# ADS1256.net
KiCad netlist of a schematic drawn in Altium Designer
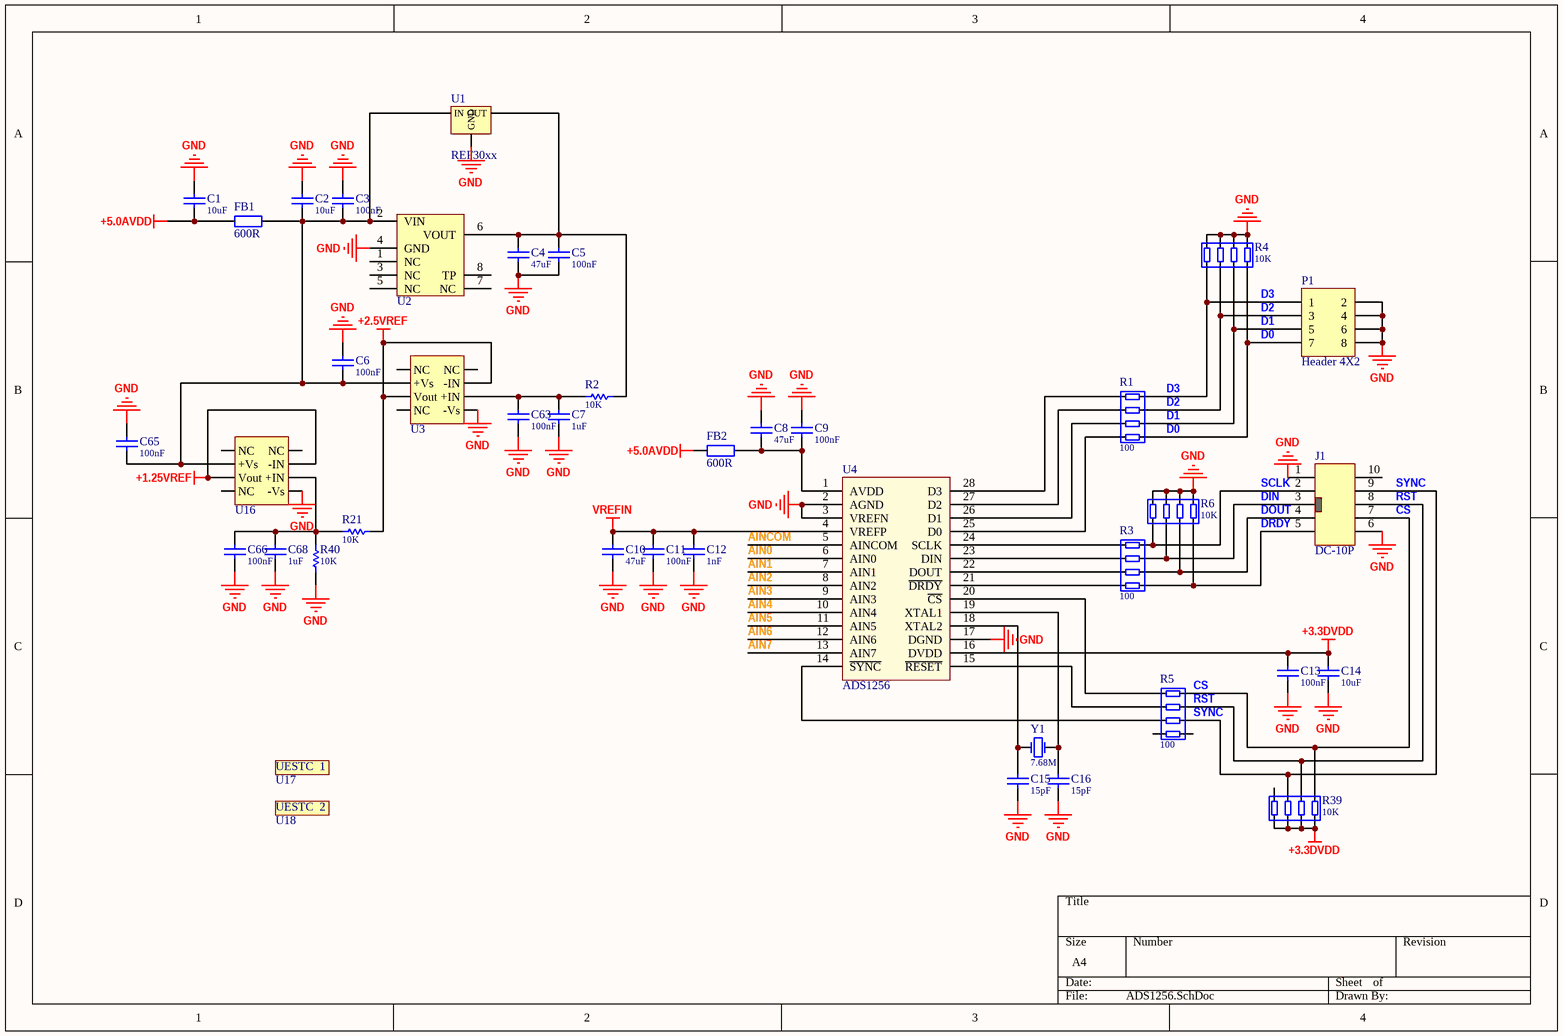
[diagram p0: ADS1256.SchDoc]

(export (version "E")
  (design (tool "Eeschema 10.0.6"))
  (components
    (comp (ref "C1")
      (value "10uF")
      (footprint "C0603-L")
      (description "贴片瓷片电容")
      (fields (field (name "Comment") "Cap-S"))
      (libsource (lib "xz_D") (part "Cap-S"))
    )
    (comp (ref "C2")
      (value "10uF")
      (footprint "C0603-L")
      (description "贴片瓷片电容")
      (fields (field (name "Comment") "Cap-S"))
      (libsource (lib "xz_D") (part "Cap-S"))
    )
    (comp (ref "C3")
      (value "100nF")
      (footprint "C0402-L")
      (description "贴片瓷片电容")
      (fields (field (name "Comment") "Cap-S"))
      (libsource (lib "xz_D") (part "Cap-S"))
    )
    (comp (ref "C4")
      (value "47uF")
      (footprint "C0805-L")
      (description "贴片瓷片电容")
      (fields (field (name "Comment") "Cap-S"))
      (libsource (lib "xz_D") (part "Cap-S"))
    )
    (comp (ref "C5")
      (value "100nF")
      (footprint "C0402-L")
      (description "贴片瓷片电容")
      (fields (field (name "Comment") "Cap-S"))
      (libsource (lib "xz_D") (part "Cap-S"))
    )
    (comp (ref "C6")
      (value "100nF")
      (footprint "C0402-L")
      (description "贴片瓷片电容")
      (fields (field (name "Comment") "Cap-S"))
      (libsource (lib "xz_D") (part "Cap-S"))
    )
    (comp (ref "C7")
      (value "1uF")
      (footprint "C0603-L")
      (description "贴片瓷片电容")
      (fields (field (name "Comment") "Cap-S"))
      (libsource (lib "xz_D") (part "Cap-S"))
    )
    (comp (ref "C8")
      (value "47uF")
      (footprint "C0805-L")
      (description "贴片瓷片电容")
      (fields (field (name "Comment") "Cap-S"))
      (libsource (lib "xz_D") (part "Cap-S"))
    )
    (comp (ref "C9")
      (value "100nF")
      (footprint "C0402-L")
      (description "贴片瓷片电容")
      (fields (field (name "Comment") "Cap-S"))
      (libsource (lib "xz_D") (part "Cap-S"))
    )
    (comp (ref "C10")
      (value "47uF")
      (footprint "C0805-L")
      (description "贴片瓷片电容")
      (fields (field (name "Comment") "Cap-S"))
      (libsource (lib "xz_D") (part "Cap-S"))
    )
    (comp (ref "C11")
      (value "100nF")
      (footprint "C0402-L")
      (description "贴片瓷片电容")
      (fields (field (name "Comment") "Cap-S"))
      (libsource (lib "xz_D") (part "Cap-S"))
    )
    (comp (ref "C12")
      (value "1nF")
      (footprint "C0402-L")
      (description "贴片瓷片电容")
      (fields (field (name "Comment") "Cap-S"))
      (libsource (lib "xz_D") (part "Cap-S"))
    )
    (comp (ref "C13")
      (value "100nF")
      (footprint "C0402-L")
      (description "贴片瓷片电容")
      (fields (field (name "Comment") "Cap-S"))
      (libsource (lib "xz_D") (part "Cap-S"))
    )
    (comp (ref "C14")
      (value "10uF")
      (footprint "C0603-L")
      (description "贴片瓷片电容")
      (fields (field (name "Comment") "Cap-S"))
      (libsource (lib "xz_D") (part "Cap-S"))
    )
    (comp (ref "C15")
      (value "15pF")
      (footprint "C0603-L")
      (description "贴片瓷片电容")
      (fields (field (name "Comment") "Cap-S"))
      (libsource (lib "xz_D") (part "Cap-S"))
    )
    (comp (ref "C16")
      (value "15pF")
      (footprint "C0603-L")
      (description "贴片瓷片电容")
      (fields (field (name "Comment") "Cap-S"))
      (libsource (lib "xz_D") (part "Cap-S"))
    )
    (comp (ref "C63")
      (value "100nF")
      (footprint "C0402-L")
      (description "贴片瓷片电容")
      (fields (field (name "Comment") "Cap-S"))
      (libsource (lib "xz_D") (part "Cap-S"))
    )
    (comp (ref "C65")
      (value "100nF")
      (footprint "C0402-L")
      (description "贴片瓷片电容")
      (fields (field (name "Comment") "Cap-S"))
      (libsource (lib "xz_D") (part "Cap-S"))
    )
    (comp (ref "C66")
      (value "100nF")
      (footprint "C0402-L")
      (description "贴片瓷片电容")
      (fields (field (name "Comment") "Cap-S"))
      (libsource (lib "xz_D") (part "Cap-S"))
    )
    (comp (ref "C68")
      (value "1uF")
      (footprint "C0603-L")
      (description "贴片瓷片电容")
      (fields (field (name "Comment") "Cap-S"))
      (libsource (lib "xz_D") (part "Cap-S"))
    )
    (comp (ref "FB1") (value "600R") (footprint "FB-0805") (libsource (lib "CommonUsed") (part "FB")))
    (comp (ref "FB2") (value "600R") (footprint "FB-0805") (libsource (lib "CommonUsed") (part "FB")))
    (comp (ref "J1") (value "DC-10P") (footprint "DC-10P") (libsource (lib "CommonUsed") (part "DC-10P")))
    (comp (ref "P1")
      (value "Header 4X2")
      (footprint "HDR2X4")
      (description "Header, 4-Pin, Dual row")
      (fields (field (name "PUBLISHER") "Altium Limited"))
      (libsource (lib "xz_C") (part "Header 4X2"))
    )
    (comp (ref "R1")
      (value "100")
      (footprint "R0603X4")
      (description "排阻 4")
      (fields (field (name "Comment") "R"))
      (libsource (lib "xz_D") (part "Res-4R"))
    )
    (comp (ref "R2")
      (value "10K")
      (footprint "R0603-L")
      (description "贴片电阻")
      (fields (field (name "Comment") "R"))
      (libsource (lib "xz_D") (part "Res"))
    )
    (comp (ref "R3")
      (value "100")
      (footprint "R0603X4")
      (description "排阻 4")
      (fields (field (name "Comment") "R"))
      (libsource (lib "xz_D") (part "Res-4R"))
    )
    (comp (ref "R4")
      (value "10K")
      (footprint "R0603X4")
      (description "排阻 4")
      (fields (field (name "Comment") "R"))
      (libsource (lib "xz_D") (part "Res-4R"))
    )
    (comp (ref "R5")
      (value "100")
      (footprint "R0603X4")
      (description "排阻 4")
      (fields (field (name "Comment") "R"))
      (libsource (lib "xz_D") (part "Res-4R"))
    )
    (comp (ref "R6")
      (value "10K")
      (footprint "R0603X4")
      (description "排阻 4")
      (fields (field (name "Comment") "R"))
      (libsource (lib "xz_D") (part "Res-4R"))
    )
    (comp (ref "R21")
      (value "10K")
      (footprint "R0603-L")
      (description "贴片电阻")
      (fields (field (name "Comment") "R"))
      (libsource (lib "xz_D") (part "Res"))
    )
    (comp (ref "R39")
      (value "10K")
      (footprint "R0603X4")
      (description "排阻 4")
      (fields (field (name "Comment") "R"))
      (libsource (lib "xz_D") (part "Res-4R"))
    )
    (comp (ref "R40")
      (value "10K")
      (footprint "R0603-L")
      (description "贴片电阻")
      (fields (field (name "Comment") "R"))
      (libsource (lib "xz_D") (part "Res"))
    )
    (comp (ref "U1")
      (value "REF30xx")
      (footprint "SOT23-3_L")
      (description "采用 SOT23-3 封装的 2.5V 输出 50ppm/℃ 漂移 50uA 静态电流的（带隙）电压参考")
      (libsource (lib "CommonUsed") (part "REF3025"))
    )
    (comp (ref "U2")
      (value "ADR45xx")
      (footprint "SOIC-8_N")
      (description "超低噪声、高精度  基准电压源")
      (libsource (lib "xz_D") (part "ADR45xx"))
    )
    (comp (ref "U3")
      (value "OPA657")
      (footprint "SOIC-8_N")
      (description "1.6-GHz, Low-Noise, FET-Input Operational Amplifier")
      (fields (field (name "MANUFACTURER") "Texas Instruments") (field (name "PARTNUMBER") "OPA656U"))
      (libsource (lib "xz_D") (part "OPA657"))
    )
    (comp (ref "U4") (value "ADS1256") (footprint "TSSOP-28") (libsource (lib "CommonUsed") (part "ADS1256")))
    (comp (ref "U16")
      (value "OPA657")
      (footprint "SOIC-8_N")
      (description "1.6-GHz, Low-Noise, FET-Input Operational Amplifier")
      (fields (field (name "MANUFACTURER") "Texas Instruments") (field (name "PARTNUMBER") "OPA656U"))
      (libsource (lib "xz_D") (part "OPA657"))
    )
    (comp (ref "U17") (value "UESTC  1") (footprint "UESTC") (libsource (lib "CommonUsed") (part "UESTC  1")))
    (comp (ref "U18")
      (value "UESTC  2")
      (footprint "UESTC  2")
      (libsource (lib "CommonUsed") (part "UESTC  2"))
    )
    (comp (ref "Y1")
      (value "7.68M")
      (footprint "XTAL-PB2-SMD")
      (description "晶振")
      (fields (field (name "Comment") "XTAL"))
      (libsource (lib "xz_D") (part "XTAL"))
    )
  )
  (nets
    (net (code "1") (name "+1.25VREF") (class "Default")
      (node (ref "U16") (pin "2") (pinfunction "-IN_2") (pintype "passive"))
      (node (ref "U16") (pin "6") (pinfunction "Vout_6") (pintype "passive"))
    )
    (net (code "2") (name "+2.5VREF") (class "Default")
      (node (ref "R21") (pin "2") (pinfunction "2_2") (pintype "passive"))
      (node (ref "U3") (pin "2") (pinfunction "-IN_2") (pintype "passive"))
      (node (ref "U3") (pin "6") (pinfunction "Vout_6") (pintype "passive"))
    )
    (net (code "3") (name "+3.3DVDD") (class "Default")
      (node (ref "C13") (pin "2") (pinfunction "2_2") (pintype "passive"))
      (node (ref "C14") (pin "2") (pinfunction "2_2") (pintype "passive"))
      (node (ref "R39") (pin "1") (pintype "passive"))
      (node (ref "R39") (pin "2") (pintype "passive"))
      (node (ref "R39") (pin "3") (pintype "passive"))
      (node (ref "R39") (pin "4") (pintype "passive"))
      (node (ref "U4") (pin "16") (pinfunction "DVDD_16") (pintype "passive"))
    )
    (net (code "4") (name "+5.0AVDD") (class "Default")
      (node (ref "C1") (pin "1") (pinfunction "1_1") (pintype "passive"))
      (node (ref "FB1") (pin "1") (pinfunction "1_1") (pintype "passive"))
      (node (ref "FB2") (pin "1") (pinfunction "1_1") (pintype "passive"))
    )
    (net (code "5") (name "/AIN0") (class "Default")
      (node (ref "U4") (pin "6") (pinfunction "AIN0_6") (pintype "passive"))
    )
    (net (code "6") (name "/AIN1") (class "Default")
      (node (ref "U4") (pin "7") (pinfunction "AIN1_7") (pintype "passive"))
    )
    (net (code "7") (name "/AIN2") (class "Default")
      (node (ref "U4") (pin "8") (pinfunction "AIN2_8") (pintype "passive"))
    )
    (net (code "8") (name "/AIN3") (class "Default")
      (node (ref "U4") (pin "9") (pinfunction "AIN3_9") (pintype "passive"))
    )
    (net (code "9") (name "/AIN4") (class "Default")
      (node (ref "U4") (pin "10") (pinfunction "AIN4_10") (pintype "passive"))
    )
    (net (code "10") (name "/AIN5") (class "Default")
      (node (ref "U4") (pin "11") (pinfunction "AIN5_11") (pintype "passive"))
    )
    (net (code "11") (name "/AIN6") (class "Default")
      (node (ref "U4") (pin "12") (pinfunction "AIN6_12") (pintype "passive"))
    )
    (net (code "12") (name "/AIN7") (class "Default")
      (node (ref "U4") (pin "13") (pinfunction "AIN7_13") (pintype "passive"))
    )
    (net (code "13") (name "/AINCOM") (class "Default")
      (node (ref "U4") (pin "5") (pinfunction "AINCOM_5") (pintype "passive"))
    )
    (net (code "14") (name "/CS") (class "Default")
      (node (ref "J1") (pin "7") (pinfunction "7_7") (pintype "passive"))
      (node (ref "R39") (pin "8") (pintype "passive"))
      (node (ref "R5") (pin "8") (pintype "passive"))
    )
    (net (code "15") (name "/D0") (class "Default")
      (node (ref "P1") (pin "7") (pinfunction "7_7") (pintype "passive"))
      (node (ref "R1") (pin "5") (pintype "passive"))
      (node (ref "R4") (pin "1") (pintype "passive"))
    )
    (net (code "16") (name "/D1") (class "Default")
      (node (ref "P1") (pin "5") (pinfunction "5_5") (pintype "passive"))
      (node (ref "R1") (pin "6") (pintype "passive"))
      (node (ref "R4") (pin "2") (pintype "passive"))
    )
    (net (code "17") (name "/D2") (class "Default")
      (node (ref "P1") (pin "3") (pinfunction "3_3") (pintype "passive"))
      (node (ref "R1") (pin "7") (pintype "passive"))
      (node (ref "R4") (pin "3") (pintype "passive"))
    )
    (net (code "18") (name "/D3") (class "Default")
      (node (ref "P1") (pin "1") (pinfunction "1_1") (pintype "passive"))
      (node (ref "R1") (pin "8") (pintype "passive"))
      (node (ref "R4") (pin "4") (pintype "passive"))
    )
    (net (code "19") (name "/DIN") (class "Default")
      (node (ref "J1") (pin "3") (pinfunction "3_3") (pintype "passive"))
      (node (ref "R3") (pin "7") (pintype "passive"))
      (node (ref "R6") (pin "3") (pintype "passive"))
    )
    (net (code "20") (name "/DOUT") (class "Default")
      (node (ref "J1") (pin "4") (pinfunction "4_4") (pintype "passive"))
      (node (ref "R3") (pin "6") (pintype "passive"))
      (node (ref "R6") (pin "2") (pintype "passive"))
    )
    (net (code "21") (name "/DRDY") (class "Default")
      (node (ref "J1") (pin "5") (pinfunction "5_5") (pintype "passive"))
      (node (ref "R3") (pin "5") (pintype "passive"))
      (node (ref "R6") (pin "1") (pintype "passive"))
    )
    (net (code "22") (name "/RST") (class "Default")
      (node (ref "J1") (pin "8") (pinfunction "8_8") (pintype "passive"))
      (node (ref "R39") (pin "7") (pintype "passive"))
      (node (ref "R5") (pin "7") (pintype "passive"))
    )
    (net (code "23") (name "/SCLK") (class "Default")
      (node (ref "J1") (pin "2") (pinfunction "2_2") (pintype "passive"))
      (node (ref "R3") (pin "8") (pintype "passive"))
      (node (ref "R6") (pin "4") (pintype "passive"))
    )
    (net (code "24") (name "/SYNC") (class "Default")
      (node (ref "J1") (pin "9") (pinfunction "9_9") (pintype "passive"))
      (node (ref "R39") (pin "6") (pintype "passive"))
      (node (ref "R5") (pin "6") (pintype "passive"))
    )
    (net (code "25") (name "GND") (class "Default")
      (node (ref "C1") (pin "2") (pinfunction "2_2") (pintype "passive"))
      (node (ref "C10") (pin "2") (pinfunction "2_2") (pintype "passive"))
      (node (ref "C11") (pin "1") (pinfunction "1_1") (pintype "passive"))
      (node (ref "C12") (pin "1") (pinfunction "1_1") (pintype "passive"))
      (node (ref "C13") (pin "1") (pinfunction "1_1") (pintype "passive"))
      (node (ref "C14") (pin "1") (pinfunction "1_1") (pintype "passive"))
      (node (ref "C15") (pin "2") (pinfunction "2_2") (pintype "passive"))
      (node (ref "C16") (pin "2") (pinfunction "2_2") (pintype "passive"))
      (node (ref "C2") (pin "2") (pinfunction "2_2") (pintype "passive"))
      (node (ref "C3") (pin "1") (pinfunction "1_1") (pintype "passive"))
      (node (ref "C4") (pin "1") (pinfunction "1_1") (pintype "passive"))
      (node (ref "C5") (pin "1") (pinfunction "1_1") (pintype "passive"))
      (node (ref "C6") (pin "1") (pinfunction "1_1") (pintype "passive"))
      (node (ref "C63") (pin "1") (pinfunction "1_1") (pintype "passive"))
      (node (ref "C65") (pin "1") (pinfunction "1_1") (pintype "passive"))
      (node (ref "C66") (pin "1") (pinfunction "1_1") (pintype "passive"))
      (node (ref "C68") (pin "1") (pinfunction "1_1") (pintype "passive"))
      (node (ref "C7") (pin "1") (pinfunction "1_1") (pintype "passive"))
      (node (ref "C8") (pin "2") (pinfunction "2_2") (pintype "passive"))
      (node (ref "C9") (pin "1") (pinfunction "1_1") (pintype "passive"))
      (node (ref "J1") (pin "1") (pinfunction "1_1") (pintype "passive"))
      (node (ref "J1") (pin "6") (pinfunction "6_6") (pintype "passive"))
      (node (ref "P1") (pin "2") (pinfunction "2_2") (pintype "passive"))
      (node (ref "P1") (pin "4") (pinfunction "4_4") (pintype "passive"))
      (node (ref "P1") (pin "6") (pinfunction "6_6") (pintype "passive"))
      (node (ref "P1") (pin "8") (pinfunction "8_8") (pintype "passive"))
      (node (ref "R4") (pin "5") (pintype "passive"))
      (node (ref "R4") (pin "6") (pintype "passive"))
      (node (ref "R4") (pin "7") (pintype "passive"))
      (node (ref "R4") (pin "8") (pintype "passive"))
      (node (ref "R40") (pin "1") (pinfunction "1_1") (pintype "passive"))
      (node (ref "R6") (pin "5") (pintype "passive"))
      (node (ref "R6") (pin "6") (pintype "passive"))
      (node (ref "R6") (pin "7") (pintype "passive"))
      (node (ref "R6") (pin "8") (pintype "passive"))
      (node (ref "U1") (pin "3") (pinfunction "GND_3") (pintype "passive"))
      (node (ref "U16") (pin "4") (pinfunction "-Vs_4") (pintype "passive"))
      (node (ref "U2") (pin "4") (pinfunction "GND_4") (pintype "passive"))
      (node (ref "U3") (pin "4") (pinfunction "-Vs_4") (pintype "passive"))
      (node (ref "U4") (pin "17") (pinfunction "DGND_17") (pintype "passive"))
      (node (ref "U4") (pin "2") (pinfunction "AGND_2") (pintype "passive"))
      (node (ref "U4") (pin "3") (pinfunction "VREFN_3") (pintype "passive"))
    )
    (net (code "26") (name "Net-(U1-IN)") (class "Default")
      (node (ref "C2") (pin "1") (pinfunction "1_1") (pintype "passive"))
      (node (ref "C3") (pin "2") (pinfunction "2_2") (pintype "passive"))
      (node (ref "C6") (pin "2") (pinfunction "2_2") (pintype "passive"))
      (node (ref "C65") (pin "2") (pinfunction "2_2") (pintype "passive"))
      (node (ref "FB1") (pin "2") (pinfunction "2_2") (pintype "passive"))
      (node (ref "U1") (pin "1") (pinfunction "IN_1") (pintype "passive"))
      (node (ref "U16") (pin "7") (pinfunction "+Vs_7") (pintype "passive"))
      (node (ref "U2") (pin "2") (pinfunction "VIN_2") (pintype "passive"))
      (node (ref "U3") (pin "7") (pinfunction "+Vs_7") (pintype "passive"))
    )
    (net (code "27") (name "Net-(U1-OUT)") (class "Default")
      (node (ref "C4") (pin "2") (pinfunction "2_2") (pintype "passive"))
      (node (ref "C5") (pin "2") (pinfunction "2_2") (pintype "passive"))
      (node (ref "R2") (pin "2") (pinfunction "2_2") (pintype "passive"))
      (node (ref "U1") (pin "2") (pinfunction "OUT_2") (pintype "passive"))
      (node (ref "U2") (pin "6") (pinfunction "VOUT_6") (pintype "passive"))
    )
    (net (code "28") (name "Net-(U3-+IN)") (class "Default")
      (node (ref "C63") (pin "2") (pinfunction "2_2") (pintype "passive"))
      (node (ref "C7") (pin "2") (pinfunction "2_2") (pintype "passive"))
      (node (ref "R2") (pin "1") (pinfunction "1_1") (pintype "passive"))
      (node (ref "U3") (pin "3") (pinfunction "+IN_3") (pintype "passive"))
    )
    (net (code "29") (name "Net-(U4-AVDD)") (class "Default")
      (node (ref "C8") (pin "1") (pinfunction "1_1") (pintype "passive"))
      (node (ref "C9") (pin "2") (pinfunction "2_2") (pintype "passive"))
      (node (ref "FB2") (pin "2") (pinfunction "2_2") (pintype "passive"))
      (node (ref "U4") (pin "1") (pinfunction "AVDD_1") (pintype "passive"))
    )
    (net (code "30") (name "Net-(U4-D0)") (class "Default")
      (node (ref "R1") (pin "4") (pintype "passive"))
      (node (ref "U4") (pin "25") (pinfunction "D0_25") (pintype "passive"))
    )
    (net (code "31") (name "Net-(U4-D1)") (class "Default")
      (node (ref "R1") (pin "3") (pintype "passive"))
      (node (ref "U4") (pin "26") (pinfunction "D1_26") (pintype "passive"))
    )
    (net (code "32") (name "Net-(U4-D2)") (class "Default")
      (node (ref "R1") (pin "2") (pintype "passive"))
      (node (ref "U4") (pin "27") (pinfunction "D2_27") (pintype "passive"))
    )
    (net (code "33") (name "Net-(U4-D3)") (class "Default")
      (node (ref "R1") (pin "1") (pintype "passive"))
      (node (ref "U4") (pin "28") (pinfunction "D3_28") (pintype "passive"))
    )
    (net (code "34") (name "Net-(U4-DIN)") (class "Default")
      (node (ref "R3") (pin "2") (pintype "passive"))
      (node (ref "U4") (pin "23") (pinfunction "DIN_23") (pintype "passive"))
    )
    (net (code "35") (name "Net-(U4-DOUT)") (class "Default")
      (node (ref "R3") (pin "3") (pintype "passive"))
      (node (ref "U4") (pin "22") (pinfunction "DOUT_22") (pintype "passive"))
    )
    (net (code "36") (name "Net-(U4-SCLK)") (class "Default")
      (node (ref "R3") (pin "1") (pintype "passive"))
      (node (ref "U4") (pin "24") (pinfunction "SCLK_24") (pintype "passive"))
    )
    (net (code "37") (name "Net-(U4-XTAL1)") (class "Default")
      (node (ref "C16") (pin "1") (pinfunction "1_1") (pintype "passive"))
      (node (ref "U4") (pin "19") (pinfunction "XTAL1_19") (pintype "passive"))
      (node (ref "Y1") (pin "1") (pinfunction "OSC1_1") (pintype "passive"))
    )
    (net (code "38") (name "Net-(U4-XTAL2)") (class "Default")
      (node (ref "C15") (pin "1") (pinfunction "1_1") (pintype "passive"))
      (node (ref "U4") (pin "18") (pinfunction "XTAL2_18") (pintype "passive"))
      (node (ref "Y1") (pin "2") (pinfunction "OSC2_2") (pintype "passive"))
    )
    (net (code "39") (name "Net-(U4-~{CS})") (class "Default")
      (node (ref "R5") (pin "1") (pintype "passive"))
      (node (ref "U4") (pin "20") (pinfunction "~{CS}_20") (pintype "passive"))
    )
    (net (code "40") (name "Net-(U4-~{DRDY})") (class "Default")
      (node (ref "R3") (pin "4") (pintype "passive"))
      (node (ref "U4") (pin "21") (pinfunction "~{DRDY}_21") (pintype "passive"))
    )
    (net (code "41") (name "Net-(U4-~{RESET})") (class "Default")
      (node (ref "R5") (pin "2") (pintype "passive"))
      (node (ref "U4") (pin "15") (pinfunction "~{RESET}_15") (pintype "passive"))
    )
    (net (code "42") (name "Net-(U4-~{SYNC})") (class "Default")
      (node (ref "R5") (pin "3") (pintype "passive"))
      (node (ref "U4") (pin "14") (pinfunction "~{SYNC}_14") (pintype "passive"))
    )
    (net (code "43") (name "Net-(U16-+IN)") (class "Default")
      (node (ref "C66") (pin "2") (pinfunction "2_2") (pintype "passive"))
      (node (ref "C68") (pin "2") (pinfunction "2_2") (pintype "passive"))
      (node (ref "R21") (pin "1") (pinfunction "1_1") (pintype "passive"))
      (node (ref "R40") (pin "2") (pinfunction "2_2") (pintype "passive"))
      (node (ref "U16") (pin "3") (pinfunction "+IN_3") (pintype "passive"))
    )
    (net (code "44") (name "VREFIN") (class "Default")
      (node (ref "C10") (pin "1") (pinfunction "1_1") (pintype "passive"))
      (node (ref "C11") (pin "2") (pinfunction "2_2") (pintype "passive"))
      (node (ref "C12") (pin "2") (pinfunction "2_2") (pintype "passive"))
      (node (ref "U4") (pin "4") (pinfunction "VREFP_4") (pintype "passive"))
    )
    (net (code "45") (name "unconnected-(J1-Pad10)") (class "Default")
      (node (ref "J1") (pin "10") (pinfunction "10_10") (pintype "passive"))
    )
    (net (code "46") (name "unconnected-(R5-Pad4)") (class "Default")
      (node (ref "R5") (pin "4") (pintype "passive"))
    )
    (net (code "47") (name "unconnected-(R5-Pad5)") (class "Default")
      (node (ref "R5") (pin "5") (pintype "passive"))
    )
    (net (code "48") (name "unconnected-(R39-Pad5)") (class "Default")
      (node (ref "R39") (pin "5") (pintype "passive"))
    )
    (net (code "49") (name "unconnected-(U2-NC-Pad1)") (class "Default")
      (node (ref "U2") (pin "1") (pinfunction "NC_1") (pintype "passive"))
    )
    (net (code "50") (name "unconnected-(U2-NC-Pad3)") (class "Default")
      (node (ref "U2") (pin "3") (pinfunction "NC_3") (pintype "passive"))
    )
    (net (code "51") (name "unconnected-(U2-NC-Pad5)") (class "Default")
      (node (ref "U2") (pin "5") (pinfunction "NC_5") (pintype "passive"))
    )
    (net (code "52") (name "unconnected-(U2-NC-Pad7)") (class "Default")
      (node (ref "U2") (pin "7") (pinfunction "NC_7") (pintype "passive"))
    )
    (net (code "53") (name "unconnected-(U2-TP-Pad8)") (class "Default")
      (node (ref "U2") (pin "8") (pinfunction "TP_8") (pintype "passive"))
    )
    (net (code "54") (name "unconnected-(U3-NC-Pad1)") (class "Default")
      (node (ref "U3") (pin "1") (pinfunction "NC_1") (pintype "passive"))
    )
    (net (code "55") (name "unconnected-(U3-NC-Pad5)") (class "Default")
      (node (ref "U3") (pin "5") (pinfunction "NC_5") (pintype "passive"))
    )
    (net (code "56") (name "unconnected-(U3-NC-Pad8)") (class "Default")
      (node (ref "U3") (pin "8") (pinfunction "NC_8") (pintype "passive"))
    )
    (net (code "57") (name "unconnected-(U16-NC-Pad1)") (class "Default")
      (node (ref "U16") (pin "1") (pinfunction "NC_1") (pintype "passive"))
    )
    (net (code "58") (name "unconnected-(U16-NC-Pad5)") (class "Default")
      (node (ref "U16") (pin "5") (pinfunction "NC_5") (pintype "passive"))
    )
    (net (code "59") (name "unconnected-(U16-NC-Pad8)") (class "Default")
      (node (ref "U16") (pin "8") (pinfunction "NC_8") (pintype "passive"))
    )
  )
)
